# NixieCard.net
KiCad netlist of a schematic drawn in Altium Designer
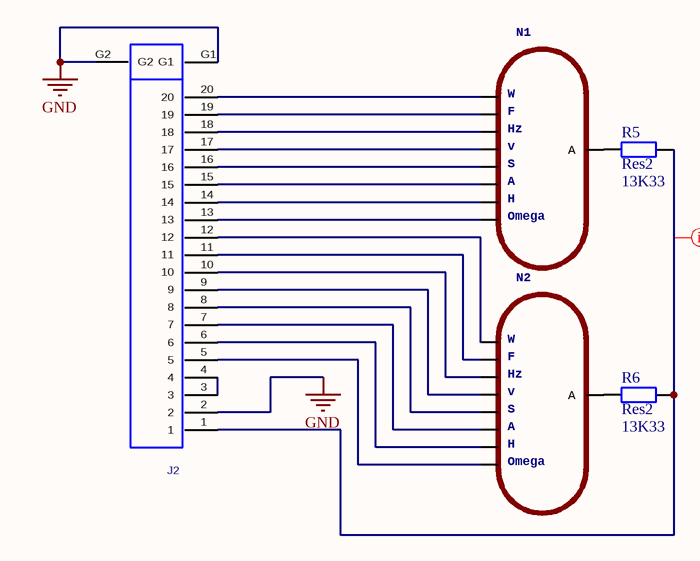
[diagram p0: NixieCard.SchDoc]

(export (version "E")
  (design (tool "Eeschema 10.0.6"))
  (components
    (comp (ref "J2")
      (value "ZF1-20-01-XX-WT")
      (footprint "ZF1-20-01-XX-WT")
      (description "ZERO INSERTION FORCE 1mm ASSEMBLY, BOTTOM CONTACT.")
      (libsource (lib "ZF1-20-01-XX-WT") (part "ZF1-20-01-XX-WT"))
    )
    (comp (ref "N1")
      (value "IN-15B")
      (footprint "IN-12")
      (description "IN-15B: medium symbol topview nixie tube")
      (fields
        (field (name "HZ") "Hz")
        (field (name "W") "W")
        (field (name "V") "v")
        (field (name "A") "A")
        (field (name "S") "S")
        (field (name "H") "H")
        (field (name "OMEGA") "Omega")
        (field (name "F") "F")
      )
      (libsource (lib "IN-15B") (part "IN-15B"))
    )
    (comp (ref "N2")
      (value "IN-15B")
      (footprint "IN-12")
      (description "IN-15B: medium symbol topview nixie tube")
      (fields
        (field (name "HZ") "Hz")
        (field (name "W") "W")
        (field (name "V") "v")
        (field (name "A") "A")
        (field (name "S") "S")
        (field (name "H") "H")
        (field (name "OMEGA") "Omega")
        (field (name "F") "F")
      )
      (libsource (lib "IN-15B") (part "IN-15B"))
    )
    (comp (ref "R5")
      (value "Res2")
      (footprint "AXIAL-0.4")
      (description "Resistor")
      (fields (field (name "ALTIUM_VALUE") "13K33") (field (name "PUBLISHER") "Altium Limited"))
      (libsource (lib "Miscellaneous Devices") (part "Res2"))
    )
    (comp (ref "R6")
      (value "Res2")
      (footprint "AXIAL-0.4")
      (description "Resistor")
      (fields (field (name "ALTIUM_VALUE") "13K33") (field (name "PUBLISHER") "Altium Limited"))
      (libsource (lib "Miscellaneous Devices") (part "Res2"))
    )
  )
  (nets
    (net (code "1") (name "GND") (class "Default")
      (node (ref "J2") (pin "2") (pinfunction "2_2") (pintype "passive"))
      (node (ref "J2") (pin "G1") (pinfunction "G1_G1") (pintype "passive"))
      (node (ref "J2") (pin "G2") (pinfunction "G2_G2") (pintype "passive"))
    )
    (net (code "2") (name "Net-(J2-Pad1)") (class "Default")
      (node (ref "J2") (pin "1") (pinfunction "1_1") (pintype "passive"))
      (node (ref "R5") (pin "1") (pinfunction "1_1") (pintype "passive"))
      (node (ref "R6") (pin "1") (pinfunction "1_1") (pintype "passive"))
    )
    (net (code "3") (name "Net-(J2-Pad3)") (class "Default")
      (node (ref "J2") (pin "3") (pinfunction "3_3") (pintype "passive"))
      (node (ref "J2") (pin "4") (pinfunction "4_4") (pintype "passive"))
    )
    (net (code "4") (name "Net-(N1-P$1)") (class "Default")
      (node (ref "J2") (pin "20") (pinfunction "20_20") (pintype "passive"))
      (node (ref "N1") (pin "0") (pinfunction "P$1_0") (pintype "passive"))
    )
    (net (code "5") (name "Net-(N1-P$2)") (class "Default")
      (node (ref "J2") (pin "19") (pinfunction "19_19") (pintype "passive"))
      (node (ref "N1") (pin "9") (pinfunction "P$2_9") (pintype "passive"))
    )
    (net (code "6") (name "Net-(N1-P$3)") (class "Default")
      (node (ref "J2") (pin "18") (pinfunction "18_18") (pintype "passive"))
      (node (ref "N1") (pin "7") (pinfunction "P$3_7") (pintype "passive"))
    )
    (net (code "7") (name "Net-(N1-P$4)") (class "Default")
      (node (ref "J2") (pin "17") (pinfunction "17_17") (pintype "passive"))
      (node (ref "N1") (pin "5") (pinfunction "P$4_5") (pintype "passive"))
    )
    (net (code "8") (name "Net-(N1-P$5)") (class "Default")
      (node (ref "J2") (pin "16") (pinfunction "16_16") (pintype "passive"))
      (node (ref "N1") (pin "4") (pinfunction "P$5_4") (pintype "passive"))
    )
    (net (code "9") (name "Net-(N1-P$6)") (class "Default")
      (node (ref "J2") (pin "15") (pinfunction "15_15") (pintype "passive"))
      (node (ref "N1") (pin "1") (pinfunction "P$6_1") (pintype "passive"))
    )
    (net (code "10") (name "Net-(N1-P$7)") (class "Default")
      (node (ref "J2") (pin "14") (pinfunction "14_14") (pintype "passive"))
      (node (ref "N1") (pin "6") (pinfunction "P$7_6") (pintype "passive"))
    )
    (net (code "11") (name "Net-(N1-P$8)") (class "Default")
      (node (ref "J2") (pin "13") (pinfunction "13_13") (pintype "passive"))
      (node (ref "N1") (pin "2") (pinfunction "P$8_2") (pintype "passive"))
    )
    (net (code "12") (name "Net-(N1-PadA)") (class "Default")
      (node (ref "N1") (pin "A") (pinfunction "A_A") (pintype "passive"))
      (node (ref "R5") (pin "2") (pinfunction "2_2") (pintype "passive"))
    )
    (net (code "13") (name "Net-(N2-P$1)") (class "Default")
      (node (ref "J2") (pin "12") (pinfunction "12_12") (pintype "passive"))
      (node (ref "N2") (pin "0") (pinfunction "P$1_0") (pintype "passive"))
    )
    (net (code "14") (name "Net-(N2-P$2)") (class "Default")
      (node (ref "J2") (pin "11") (pinfunction "11_11") (pintype "passive"))
      (node (ref "N2") (pin "9") (pinfunction "P$2_9") (pintype "passive"))
    )
    (net (code "15") (name "Net-(N2-P$3)") (class "Default")
      (node (ref "J2") (pin "10") (pinfunction "10_10") (pintype "passive"))
      (node (ref "N2") (pin "7") (pinfunction "P$3_7") (pintype "passive"))
    )
    (net (code "16") (name "Net-(N2-P$4)") (class "Default")
      (node (ref "J2") (pin "9") (pinfunction "9_9") (pintype "passive"))
      (node (ref "N2") (pin "5") (pinfunction "P$4_5") (pintype "passive"))
    )
    (net (code "17") (name "Net-(N2-P$5)") (class "Default")
      (node (ref "J2") (pin "8") (pinfunction "8_8") (pintype "passive"))
      (node (ref "N2") (pin "4") (pinfunction "P$5_4") (pintype "passive"))
    )
    (net (code "18") (name "Net-(N2-P$6)") (class "Default")
      (node (ref "J2") (pin "7") (pinfunction "7_7") (pintype "passive"))
      (node (ref "N2") (pin "1") (pinfunction "P$6_1") (pintype "passive"))
    )
    (net (code "19") (name "Net-(N2-P$7)") (class "Default")
      (node (ref "J2") (pin "6") (pinfunction "6_6") (pintype "passive"))
      (node (ref "N2") (pin "6") (pinfunction "P$7_6") (pintype "passive"))
    )
    (net (code "20") (name "Net-(N2-P$8)") (class "Default")
      (node (ref "J2") (pin "5") (pinfunction "5_5") (pintype "passive"))
      (node (ref "N2") (pin "2") (pinfunction "P$8_2") (pintype "passive"))
    )
    (net (code "21") (name "Net-(N2-PadA)") (class "Default")
      (node (ref "N2") (pin "A") (pinfunction "A_A") (pintype "passive"))
      (node (ref "R6") (pin "2") (pinfunction "2_2") (pintype "passive"))
    )
  )
)
